# Flower.net
KiCad netlist of a schematic drawn in Altium Designer
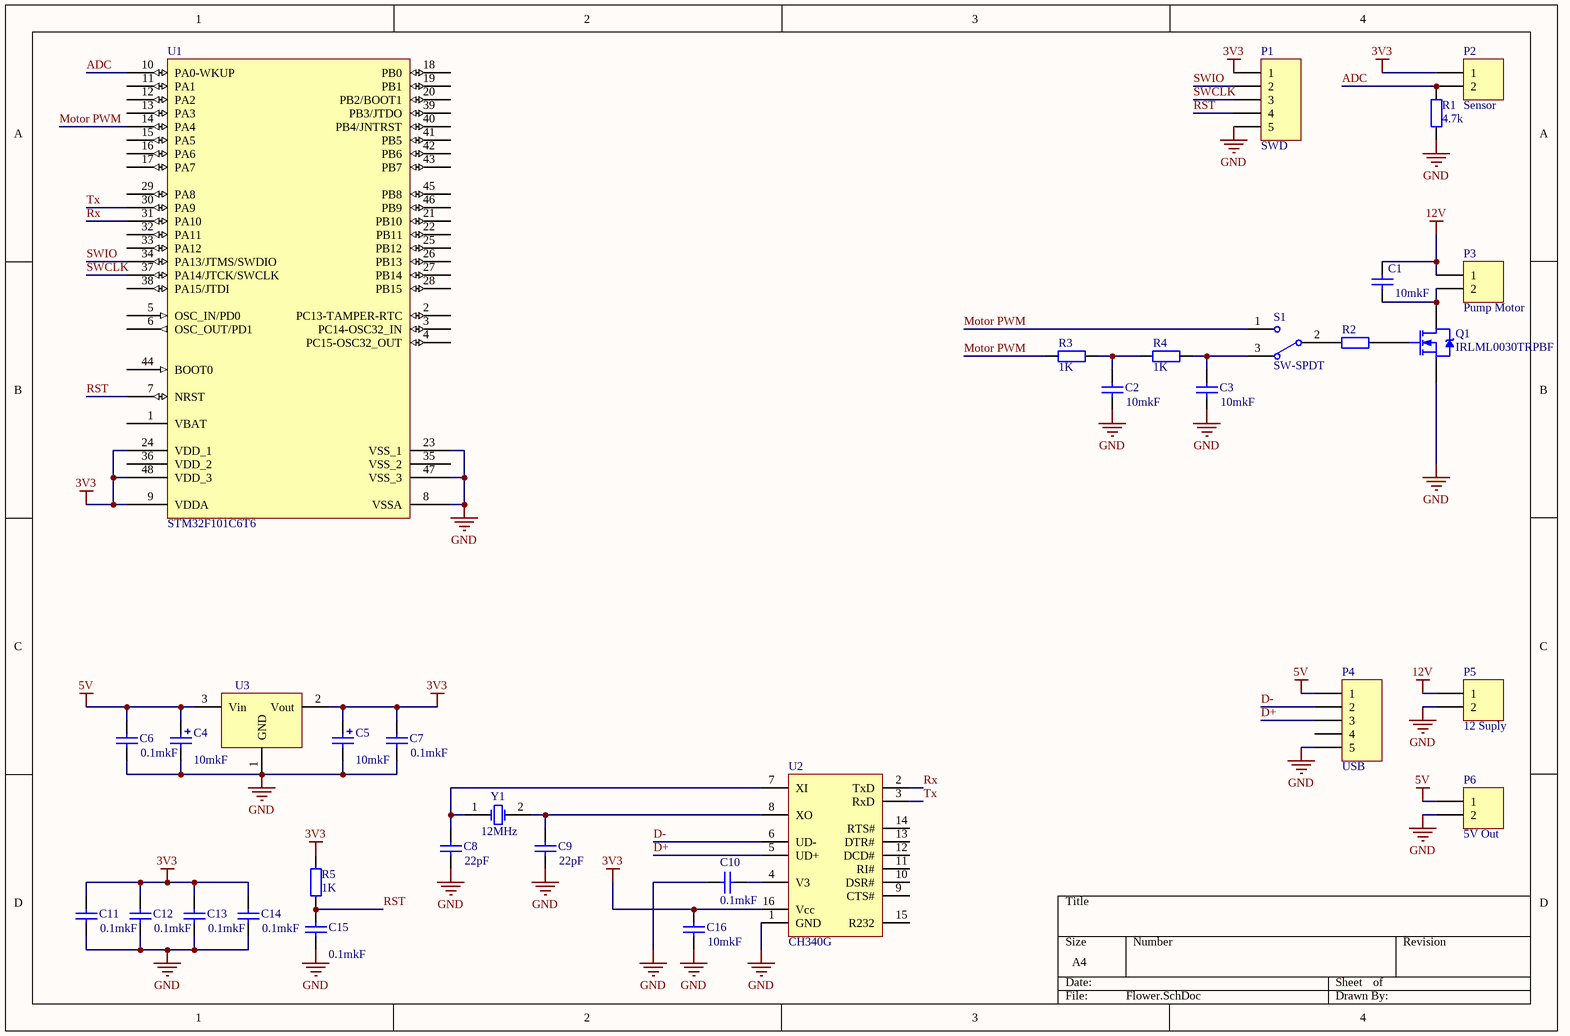
[diagram p0: Flower.SchDoc]

(export (version "E")
  (design (tool "Eeschema 10.0.6"))
  (components
    (comp (ref "C1")
      (value "10mkF")
      (footprint "CAPC2012X135N")
      (description "Capacitor (Semiconductor SIM Model)")
      (fields (field (name "PUBLISHER") "Altium Limited"))
      (libsource (lib "Miscellaneous Devices") (part "Cap Semi"))
    )
    (comp (ref "C2")
      (value "10mkF")
      (footprint "CAPC2012X135N")
      (description "Capacitor (Semiconductor SIM Model)")
      (fields (field (name "PUBLISHER") "Altium Limited"))
      (libsource (lib "Miscellaneous Devices") (part "Cap Semi"))
    )
    (comp (ref "C3")
      (value "10mkF")
      (footprint "CAPC2012X135N")
      (description "Capacitor (Semiconductor SIM Model)")
      (fields (field (name "PUBLISHER") "Altium Limited"))
      (libsource (lib "Miscellaneous Devices") (part "Cap Semi"))
    )
    (comp (ref "C4")
      (value "10mkF")
      (footprint "CAPC2012X135N")
      (description "Polarized Capacitor (Axial)")
      (fields (field (name "PUBLISHER") "Altium Limited"))
      (libsource (lib "Miscellaneous Devices") (part "Cap Pol2"))
    )
    (comp (ref "C5")
      (value "10mkF")
      (footprint "CAPC2012X135N")
      (description "Polarized Capacitor (Axial)")
      (fields (field (name "PUBLISHER") "Altium Limited"))
      (libsource (lib "Miscellaneous Devices") (part "Cap Pol2"))
    )
    (comp (ref "C6")
      (value "0.1mkF")
      (footprint "CAPC1608X90N")
      (description "Capacitor (Semiconductor SIM Model)")
      (fields (field (name "PUBLISHER") "Altium Limited"))
      (libsource (lib "Miscellaneous Devices") (part "Cap Semi"))
    )
    (comp (ref "C7")
      (value "0.1mkF")
      (footprint "CAPC1608X90N")
      (description "Capacitor (Semiconductor SIM Model)")
      (fields (field (name "PUBLISHER") "Altium Limited"))
      (libsource (lib "Miscellaneous Devices") (part "Cap Semi"))
    )
    (comp (ref "C8")
      (value "22pF")
      (footprint "CAPC1608X90N")
      (description "Capacitor (Semiconductor SIM Model)")
      (fields (field (name "PUBLISHER") "Altium Limited"))
      (libsource (lib "Miscellaneous Devices") (part "Cap Semi"))
    )
    (comp (ref "C9")
      (value "22pF")
      (footprint "CAPC1608X90N")
      (description "Capacitor (Semiconductor SIM Model)")
      (fields (field (name "PUBLISHER") "Altium Limited"))
      (libsource (lib "Miscellaneous Devices") (part "Cap Semi"))
    )
    (comp (ref "C10")
      (value "0.1mkF")
      (footprint "CAPC1608X90N")
      (description "Capacitor (Semiconductor SIM Model)")
      (fields (field (name "PUBLISHER") "Altium Limited"))
      (libsource (lib "Miscellaneous Devices") (part "Cap Semi"))
    )
    (comp (ref "C11")
      (value "0.1mkF")
      (footprint "CAPC1608X90N")
      (description "Capacitor (Semiconductor SIM Model)")
      (fields (field (name "PUBLISHER") "Altium Limited"))
      (libsource (lib "Miscellaneous Devices") (part "Cap Semi"))
    )
    (comp (ref "C12")
      (value "0.1mkF")
      (footprint "CAPC1608X90N")
      (description "Capacitor (Semiconductor SIM Model)")
      (fields (field (name "PUBLISHER") "Altium Limited"))
      (libsource (lib "Miscellaneous Devices") (part "Cap Semi"))
    )
    (comp (ref "C13")
      (value "0.1mkF")
      (footprint "CAPC1608X90N")
      (description "Capacitor (Semiconductor SIM Model)")
      (fields (field (name "PUBLISHER") "Altium Limited"))
      (libsource (lib "Miscellaneous Devices") (part "Cap Semi"))
    )
    (comp (ref "C14")
      (value "0.1mkF")
      (footprint "CAPC1608X90N")
      (description "Capacitor (Semiconductor SIM Model)")
      (fields (field (name "PUBLISHER") "Altium Limited"))
      (libsource (lib "Miscellaneous Devices") (part "Cap Semi"))
    )
    (comp (ref "C15")
      (value "0.1mkF")
      (footprint "CAPC1608X90N")
      (description "Capacitor (Semiconductor SIM Model)")
      (fields (field (name "PUBLISHER") "Altium Limited"))
      (libsource (lib "Miscellaneous Devices") (part "Cap Semi"))
    )
    (comp (ref "C16")
      (value "10mkF")
      (footprint "CAPC1608X90N")
      (description "Capacitor (Semiconductor SIM Model)")
      (fields (field (name "PUBLISHER") "Altium Limited"))
      (libsource (lib "Miscellaneous Devices") (part "Cap Semi"))
    )
    (comp (ref "P1")
      (value "SWD")
      (footprint "HDR1X5")
      (description "Header, 5-Pin")
      (fields (field (name "PUBLISHER") "Altium Limited"))
      (libsource (lib "Miscellaneous Connectors") (part "Header 5"))
    )
    (comp (ref "P2")
      (value "Sensor")
      (footprint "NXW-02SMDK")
      (description "Header, 2-Pin")
      (fields (field (name "PUBLISHER") "Altium Limited"))
      (libsource (lib "Miscellaneous Connectors") (part "Header 2"))
    )
    (comp (ref "P3")
      (value "Pump Motor")
      (footprint "NXW-02SMDK")
      (description "Header, 2-Pin")
      (fields (field (name "PUBLISHER") "Altium Limited"))
      (libsource (lib "Miscellaneous Connectors") (part "Header 2"))
    )
    (comp (ref "P4")
      (value "USB")
      (footprint "USB_Mini-B_Molex_SMT")
      (description "Header, 5-Pin")
      (fields (field (name "PUBLISHER") "Altium Limited"))
      (libsource (lib "Miscellaneous Connectors") (part "Header 5"))
    )
    (comp (ref "P5")
      (value "12 Suply")
      (footprint "NXW-02SMD")
      (description "Header, 2-Pin")
      (fields (field (name "PUBLISHER") "Altium Limited"))
      (libsource (lib "Miscellaneous Connectors") (part "Header 2"))
    )
    (comp (ref "P6")
      (value "5V Out")
      (footprint "NXW-02SMD")
      (description "Header, 2-Pin")
      (fields (field (name "PUBLISHER") "Altium Limited"))
      (libsource (lib "Miscellaneous Connectors") (part "Header 2"))
    )
    (comp (ref "Q1")
      (value "IRLML0030TRPBF")
      (footprint "SOT23-3")
      (description "N-Channel Power MOSFET")
      (fields (field (name "PUBLISHER") "Altium Limited"))
      (libsource (lib "Miscellaneous Devices") (part "NMOS-2"))
    )
    (comp (ref "R1")
      (value "4.7k")
      (footprint "RESC1608X55N")
      (description "Resistor")
      (fields (field (name "PUBLISHER") "Altium Limited"))
      (libsource (lib "Miscellaneous Devices") (part "Res2"))
    )
    (comp (ref "R2")
      (value "1K")
      (footprint "RESC1608X55N")
      (description "Resistor")
      (fields (field (name "PUBLISHER") "Altium Limited"))
      (libsource (lib "") (part "Res2_1"))
    )
    (comp (ref "R3")
      (value "1K")
      (footprint "RESC1608X55N")
      (description "Resistor")
      (fields (field (name "PUBLISHER") "Altium Limited"))
      (libsource (lib "") (part "Res2_1"))
    )
    (comp (ref "R4")
      (value "1K")
      (footprint "RESC1608X55N")
      (description "Resistor")
      (fields (field (name "PUBLISHER") "Altium Limited"))
      (libsource (lib "") (part "Res2_1"))
    )
    (comp (ref "R5")
      (value "1K")
      (footprint "RESC1608X55N")
      (description "Resistor")
      (fields (field (name "PUBLISHER") "Altium Limited"))
      (libsource (lib "Miscellaneous Devices") (part "Res2"))
    )
    (comp (ref "S1")
      (value "SW-SPDT")
      (footprint "HDR1X3")
      (description "SPDT Subminiature Toggle Switch, Right Angle Mounting, Vertical Actuation")
      (fields (field (name "PUBLISHER") "Altium Limited"))
      (libsource (lib "Miscellaneous Devices") (part "SW-SPDT"))
    )
    (comp (ref "U1")
      (value "STM32F101C6T6")
      (footprint "LQFP48_N")
      (description "STM32 ARM-based 32-bit MCU with 32 Kbytes Flash, 48-pin LQFP, Industrial Temperature")
      (fields (field (name "PUBLISHER") "Altium Limited"))
      (libsource (lib "ST Microcontroller 32-Bit STM32") (part "STM32F101C6T6"))
    )
    (comp (ref "U2")
      (value "CH340G")
      (footprint "SOIC127P600X175-16AN")
      (libsource (lib "FlowerLib") (part "CH340G"))
    )
    (comp (ref "U3") (value "LD1117") (footprint "SOT223") (libsource (lib "FlowerLib") (part "LD1117")))
    (comp (ref "Y1")
      (value "12MHz")
      (footprint "KX-X 8MHz")
      (description "Crystal Oscillator")
      (fields (field (name "Comment") "XTAL") (field (name "PUBLISHER") "Altium Limited"))
      (libsource (lib "Miscellaneous Devices") (part "XTAL"))
    )
  )
  (nets
    (net (code "1") (name "/ADC") (class "Default")
      (node (ref "P2") (pin "2") (pinfunction "2_2") (pintype "passive"))
      (node (ref "R1") (pin "2") (pinfunction "2_2") (pintype "passive"))
      (node (ref "U1") (pin "10") (pinfunction "PA0-WKUP_10") (pintype "bidirectional"))
    )
    (net (code "2") (name "/D+") (class "Default")
      (node (ref "P4") (pin "3") (pinfunction "3_3") (pintype "passive"))
      (node (ref "U2") (pin "5") (pinfunction "UD+_5") (pintype "passive"))
    )
    (net (code "3") (name "/D-") (class "Default")
      (node (ref "P4") (pin "2") (pinfunction "2_2") (pintype "passive"))
      (node (ref "U2") (pin "6") (pinfunction "UD-_6") (pintype "passive"))
    )
    (net (code "4") (name "/Motor PWM") (class "Default")
      (node (ref "R3") (pin "1") (pinfunction "1_1") (pintype "passive"))
      (node (ref "S1") (pin "1") (pinfunction "1_1") (pintype "passive"))
      (node (ref "U1") (pin "14") (pinfunction "PA4_14") (pintype "bidirectional"))
    )
    (net (code "5") (name "/RST") (class "Default")
      (node (ref "C15") (pin "2") (pinfunction "2_2") (pintype "passive"))
      (node (ref "P1") (pin "4") (pinfunction "4_4") (pintype "passive"))
      (node (ref "R5") (pin "1") (pinfunction "1_1") (pintype "passive"))
      (node (ref "U1") (pin "7") (pinfunction "NRST_7") (pintype "bidirectional"))
    )
    (net (code "6") (name "/Rx") (class "Default")
      (node (ref "U1") (pin "31") (pinfunction "PA10_31") (pintype "bidirectional"))
      (node (ref "U2") (pin "2") (pinfunction "TxD_2") (pintype "passive"))
    )
    (net (code "7") (name "/SWCLK") (class "Default")
      (node (ref "P1") (pin "3") (pinfunction "3_3") (pintype "passive"))
      (node (ref "U1") (pin "37") (pinfunction "PA14/JTCK/SWCLK_37") (pintype "bidirectional"))
    )
    (net (code "8") (name "/SWIO") (class "Default")
      (node (ref "P1") (pin "2") (pinfunction "2_2") (pintype "passive"))
      (node (ref "U1") (pin "34") (pinfunction "PA13/JTMS/SWDIO_34") (pintype "bidirectional"))
    )
    (net (code "9") (name "/Tx") (class "Default")
      (node (ref "U1") (pin "30") (pinfunction "PA9_30") (pintype "bidirectional"))
      (node (ref "U2") (pin "3") (pinfunction "RxD_3") (pintype "passive"))
    )
    (net (code "10") (name "3V3") (class "Default")
      (node (ref "C11") (pin "2") (pinfunction "2_2") (pintype "passive"))
      (node (ref "C12") (pin "2") (pinfunction "2_2") (pintype "passive"))
      (node (ref "C13") (pin "2") (pinfunction "2_2") (pintype "passive"))
      (node (ref "C14") (pin "2") (pinfunction "2_2") (pintype "passive"))
      (node (ref "C16") (pin "2") (pinfunction "2_2") (pintype "passive"))
      (node (ref "C5") (pin "1") (pinfunction "1_1") (pintype "passive"))
      (node (ref "C7") (pin "2") (pinfunction "2_2") (pintype "passive"))
      (node (ref "P1") (pin "1") (pinfunction "1_1") (pintype "passive"))
      (node (ref "P2") (pin "1") (pinfunction "1_1") (pintype "passive"))
      (node (ref "R5") (pin "2") (pinfunction "2_2") (pintype "passive"))
      (node (ref "U1") (pin "24") (pinfunction "VDD_1_24") (pintype "power_in"))
      (node (ref "U1") (pin "48") (pinfunction "VDD_3_48") (pintype "power_in"))
      (node (ref "U1") (pin "9") (pinfunction "VDDA_9") (pintype "power_in"))
      (node (ref "U2") (pin "16") (pinfunction "Vcc_16") (pintype "passive"))
      (node (ref "U3") (pin "2") (pinfunction "Vout_2") (pintype "passive"))
    )
    (net (code "11") (name "5V") (class "Default")
      (node (ref "C4") (pin "1") (pinfunction "1_1") (pintype "passive"))
      (node (ref "C6") (pin "2") (pinfunction "2_2") (pintype "passive"))
      (node (ref "P4") (pin "1") (pinfunction "1_1") (pintype "passive"))
      (node (ref "P6") (pin "1") (pinfunction "1_1") (pintype "passive"))
      (node (ref "U3") (pin "3") (pinfunction "Vin_3") (pintype "passive"))
    )
    (net (code "12") (name "12V") (class "Default")
      (node (ref "C1") (pin "2") (pinfunction "2_2") (pintype "passive"))
      (node (ref "P3") (pin "1") (pinfunction "1_1") (pintype "passive"))
      (node (ref "P5") (pin "1") (pinfunction "1_1") (pintype "passive"))
    )
    (net (code "13") (name "GND") (class "Default")
      (node (ref "C10") (pin "2") (pinfunction "2_2") (pintype "passive"))
      (node (ref "C11") (pin "1") (pinfunction "1_1") (pintype "passive"))
      (node (ref "C12") (pin "1") (pinfunction "1_1") (pintype "passive"))
      (node (ref "C13") (pin "1") (pinfunction "1_1") (pintype "passive"))
      (node (ref "C14") (pin "1") (pinfunction "1_1") (pintype "passive"))
      (node (ref "C15") (pin "1") (pinfunction "1_1") (pintype "passive"))
      (node (ref "C16") (pin "1") (pinfunction "1_1") (pintype "passive"))
      (node (ref "C2") (pin "1") (pinfunction "1_1") (pintype "passive"))
      (node (ref "C3") (pin "1") (pinfunction "1_1") (pintype "passive"))
      (node (ref "C4") (pin "2") (pinfunction "2_2") (pintype "passive"))
      (node (ref "C5") (pin "2") (pinfunction "2_2") (pintype "passive"))
      (node (ref "C6") (pin "1") (pinfunction "1_1") (pintype "passive"))
      (node (ref "C7") (pin "1") (pinfunction "1_1") (pintype "passive"))
      (node (ref "C8") (pin "1") (pinfunction "1_1") (pintype "passive"))
      (node (ref "C9") (pin "1") (pinfunction "1_1") (pintype "passive"))
      (node (ref "P1") (pin "5") (pinfunction "5_5") (pintype "passive"))
      (node (ref "P4") (pin "5") (pinfunction "5_5") (pintype "passive"))
      (node (ref "P5") (pin "2") (pinfunction "2_2") (pintype "passive"))
      (node (ref "P6") (pin "2") (pinfunction "2_2") (pintype "passive"))
      (node (ref "Q1") (pin "3") (pinfunction "S_3") (pintype "passive"))
      (node (ref "R1") (pin "1") (pinfunction "1_1") (pintype "passive"))
      (node (ref "U1") (pin "23") (pinfunction "VSS_1_23") (pintype "power_in"))
      (node (ref "U1") (pin "47") (pinfunction "VSS_3_47") (pintype "power_in"))
      (node (ref "U1") (pin "8") (pinfunction "VSSA_8") (pintype "power_in"))
      (node (ref "U2") (pin "1") (pinfunction "GND_1") (pintype "passive"))
      (node (ref "U3") (pin "1") (pinfunction "GND_1") (pintype "passive"))
    )
    (net (code "14") (name "Net-(C2-Pad2)") (class "Default")
      (node (ref "C2") (pin "2") (pinfunction "2_2") (pintype "passive"))
      (node (ref "R3") (pin "2") (pinfunction "2_2") (pintype "passive"))
      (node (ref "R4") (pin "1") (pinfunction "1_1") (pintype "passive"))
    )
    (net (code "15") (name "Net-(C3-Pad2)") (class "Default")
      (node (ref "C3") (pin "2") (pinfunction "2_2") (pintype "passive"))
      (node (ref "R4") (pin "2") (pinfunction "2_2") (pintype "passive"))
      (node (ref "S1") (pin "3") (pinfunction "3_3") (pintype "passive"))
    )
    (net (code "16") (name "Net-(Q1-D)") (class "Default")
      (node (ref "C1") (pin "1") (pinfunction "1_1") (pintype "passive"))
      (node (ref "P3") (pin "2") (pinfunction "2_2") (pintype "passive"))
      (node (ref "Q1") (pin "2") (pinfunction "D_2") (pintype "passive"))
    )
    (net (code "17") (name "Net-(Q1-G)") (class "Default")
      (node (ref "Q1") (pin "1") (pinfunction "G_1") (pintype "passive"))
      (node (ref "R2") (pin "2") (pinfunction "2_2") (pintype "passive"))
    )
    (net (code "18") (name "Net-(R2-Pad1)") (class "Default")
      (node (ref "R2") (pin "1") (pinfunction "1_1") (pintype "passive"))
      (node (ref "S1") (pin "2") (pinfunction "2_2") (pintype "passive"))
    )
    (net (code "19") (name "Net-(U2-V3)") (class "Default")
      (node (ref "C10") (pin "1") (pinfunction "1_1") (pintype "passive"))
      (node (ref "U2") (pin "4") (pinfunction "V3_4") (pintype "passive"))
    )
    (net (code "20") (name "Net-(U2-XI)") (class "Default")
      (node (ref "C8") (pin "2") (pinfunction "2_2") (pintype "passive"))
      (node (ref "U2") (pin "7") (pinfunction "XI_7") (pintype "passive"))
      (node (ref "Y1") (pin "1") (pinfunction "OSC1_1") (pintype "passive"))
    )
    (net (code "21") (name "Net-(U2-XO)") (class "Default")
      (node (ref "C9") (pin "2") (pinfunction "2_2") (pintype "passive"))
      (node (ref "U2") (pin "8") (pinfunction "XO_8") (pintype "passive"))
      (node (ref "Y1") (pin "2") (pinfunction "OSC2_2") (pintype "passive"))
    )
    (net (code "22") (name "unconnected-(P4-Pad4)") (class "Default")
      (node (ref "P4") (pin "4") (pinfunction "4_4") (pintype "passive"))
    )
    (net (code "23") (name "unconnected-(U1-BOOT0-Pad44)") (class "Default")
      (node (ref "U1") (pin "44") (pinfunction "BOOT0_44") (pintype "input"))
    )
    (net (code "24") (name "unconnected-(U1-OSC_IN{slash}PD0-Pad5)") (class "Default")
      (node (ref "U1") (pin "5") (pinfunction "OSC_IN/PD0_5") (pintype "input"))
    )
    (net (code "25") (name "unconnected-(U1-OSC_OUT{slash}PD1-Pad6)") (class "Default")
      (node (ref "U1") (pin "6") (pinfunction "OSC_OUT/PD1_6") (pintype "output"))
    )
    (net (code "26") (name "unconnected-(U1-PA1-Pad11)") (class "Default")
      (node (ref "U1") (pin "11") (pinfunction "PA1_11") (pintype "bidirectional"))
    )
    (net (code "27") (name "unconnected-(U1-PA2-Pad12)") (class "Default")
      (node (ref "U1") (pin "12") (pinfunction "PA2_12") (pintype "bidirectional"))
    )
    (net (code "28") (name "unconnected-(U1-PA3-Pad13)") (class "Default")
      (node (ref "U1") (pin "13") (pinfunction "PA3_13") (pintype "bidirectional"))
    )
    (net (code "29") (name "unconnected-(U1-PA5-Pad15)") (class "Default")
      (node (ref "U1") (pin "15") (pinfunction "PA5_15") (pintype "bidirectional"))
    )
    (net (code "30") (name "unconnected-(U1-PA6-Pad16)") (class "Default")
      (node (ref "U1") (pin "16") (pinfunction "PA6_16") (pintype "bidirectional"))
    )
    (net (code "31") (name "unconnected-(U1-PA7-Pad17)") (class "Default")
      (node (ref "U1") (pin "17") (pinfunction "PA7_17") (pintype "bidirectional"))
    )
    (net (code "32") (name "unconnected-(U1-PA8-Pad29)") (class "Default")
      (node (ref "U1") (pin "29") (pinfunction "PA8_29") (pintype "bidirectional"))
    )
    (net (code "33") (name "unconnected-(U1-PA11-Pad32)") (class "Default")
      (node (ref "U1") (pin "32") (pinfunction "PA11_32") (pintype "bidirectional"))
    )
    (net (code "34") (name "unconnected-(U1-PA12-Pad33)") (class "Default")
      (node (ref "U1") (pin "33") (pinfunction "PA12_33") (pintype "bidirectional"))
    )
    (net (code "35") (name "unconnected-(U1-PA15{slash}JTDI-Pad38)") (class "Default")
      (node (ref "U1") (pin "38") (pinfunction "PA15/JTDI_38") (pintype "bidirectional"))
    )
    (net (code "36") (name "unconnected-(U1-PB0-Pad18)") (class "Default")
      (node (ref "U1") (pin "18") (pinfunction "PB0_18") (pintype "bidirectional"))
    )
    (net (code "37") (name "unconnected-(U1-PB1-Pad19)") (class "Default")
      (node (ref "U1") (pin "19") (pinfunction "PB1_19") (pintype "bidirectional"))
    )
    (net (code "38") (name "unconnected-(U1-PB2{slash}BOOT1-Pad20)") (class "Default")
      (node (ref "U1") (pin "20") (pinfunction "PB2/BOOT1_20") (pintype "bidirectional"))
    )
    (net (code "39") (name "unconnected-(U1-PB3{slash}JTDO-Pad39)") (class "Default")
      (node (ref "U1") (pin "39") (pinfunction "PB3/JTDO_39") (pintype "bidirectional"))
    )
    (net (code "40") (name "unconnected-(U1-PB4{slash}JNTRST-Pad40)") (class "Default")
      (node (ref "U1") (pin "40") (pinfunction "PB4/JNTRST_40") (pintype "bidirectional"))
    )
    (net (code "41") (name "unconnected-(U1-PB5-Pad41)") (class "Default")
      (node (ref "U1") (pin "41") (pinfunction "PB5_41") (pintype "bidirectional"))
    )
    (net (code "42") (name "unconnected-(U1-PB6-Pad42)") (class "Default")
      (node (ref "U1") (pin "42") (pinfunction "PB6_42") (pintype "bidirectional"))
    )
    (net (code "43") (name "unconnected-(U1-PB7-Pad43)") (class "Default")
      (node (ref "U1") (pin "43") (pinfunction "PB7_43") (pintype "bidirectional"))
    )
    (net (code "44") (name "unconnected-(U1-PB8-Pad45)") (class "Default")
      (node (ref "U1") (pin "45") (pinfunction "PB8_45") (pintype "bidirectional"))
    )
    (net (code "45") (name "unconnected-(U1-PB9-Pad46)") (class "Default")
      (node (ref "U1") (pin "46") (pinfunction "PB9_46") (pintype "bidirectional"))
    )
    (net (code "46") (name "unconnected-(U1-PB10-Pad21)") (class "Default")
      (node (ref "U1") (pin "21") (pinfunction "PB10_21") (pintype "bidirectional"))
    )
    (net (code "47") (name "unconnected-(U1-PB11-Pad22)") (class "Default")
      (node (ref "U1") (pin "22") (pinfunction "PB11_22") (pintype "bidirectional"))
    )
    (net (code "48") (name "unconnected-(U1-PB12-Pad25)") (class "Default")
      (node (ref "U1") (pin "25") (pinfunction "PB12_25") (pintype "bidirectional"))
    )
    (net (code "49") (name "unconnected-(U1-PB13-Pad26)") (class "Default")
      (node (ref "U1") (pin "26") (pinfunction "PB13_26") (pintype "bidirectional"))
    )
    (net (code "50") (name "unconnected-(U1-PB14-Pad27)") (class "Default")
      (node (ref "U1") (pin "27") (pinfunction "PB14_27") (pintype "bidirectional"))
    )
    (net (code "51") (name "unconnected-(U1-PB15-Pad28)") (class "Default")
      (node (ref "U1") (pin "28") (pinfunction "PB15_28") (pintype "bidirectional"))
    )
    (net (code "52") (name "unconnected-(U1-PC13-TAMPER-RTC-Pad2)") (class "Default")
      (node (ref "U1") (pin "2") (pinfunction "PC13-TAMPER-RTC_2") (pintype "bidirectional"))
    )
    (net (code "53") (name "unconnected-(U1-PC14-OSC32_IN-Pad3)") (class "Default")
      (node (ref "U1") (pin "3") (pinfunction "PC14-OSC32_IN_3") (pintype "bidirectional"))
    )
    (net (code "54") (name "unconnected-(U1-PC15-OSC32_OUT-Pad4)") (class "Default")
      (node (ref "U1") (pin "4") (pinfunction "PC15-OSC32_OUT_4") (pintype "bidirectional"))
    )
    (net (code "55") (name "unconnected-(U1-VBAT-Pad1)") (class "Default")
      (node (ref "U1") (pin "1") (pinfunction "VBAT_1") (pintype "power_in"))
    )
    (net (code "56") (name "unconnected-(U1-VDD_2-Pad36)") (class "Default")
      (node (ref "U1") (pin "36") (pinfunction "VDD_2_36") (pintype "power_in"))
    )
    (net (code "57") (name "unconnected-(U1-VSS_2-Pad35)") (class "Default")
      (node (ref "U1") (pin "35") (pinfunction "VSS_2_35") (pintype "power_in"))
    )
    (net (code "58") (name "unconnected-(U2-CTS#-Pad9)") (class "Default")
      (node (ref "U2") (pin "9") (pinfunction "CTS#_9") (pintype "passive"))
    )
    (net (code "59") (name "unconnected-(U2-DCD#-Pad12)") (class "Default")
      (node (ref "U2") (pin "12") (pinfunction "DCD#_12") (pintype "passive"))
    )
    (net (code "60") (name "unconnected-(U2-DSR#-Pad10)") (class "Default")
      (node (ref "U2") (pin "10") (pinfunction "DSR#_10") (pintype "passive"))
    )
    (net (code "61") (name "unconnected-(U2-DTR#-Pad13)") (class "Default")
      (node (ref "U2") (pin "13") (pinfunction "DTR#_13") (pintype "passive"))
    )
    (net (code "62") (name "unconnected-(U2-R232-Pad15)") (class "Default")
      (node (ref "U2") (pin "15") (pinfunction "R232_15") (pintype "passive"))
    )
    (net (code "63") (name "unconnected-(U2-RI#-Pad11)") (class "Default")
      (node (ref "U2") (pin "11") (pinfunction "RI#_11") (pintype "passive"))
    )
    (net (code "64") (name "unconnected-(U2-RTS#-Pad14)") (class "Default")
      (node (ref "U2") (pin "14") (pinfunction "RTS#_14") (pintype "passive"))
    )
  )
)
